# simple-hat.net
KiCad netlist of a schematic drawn in EAGLE
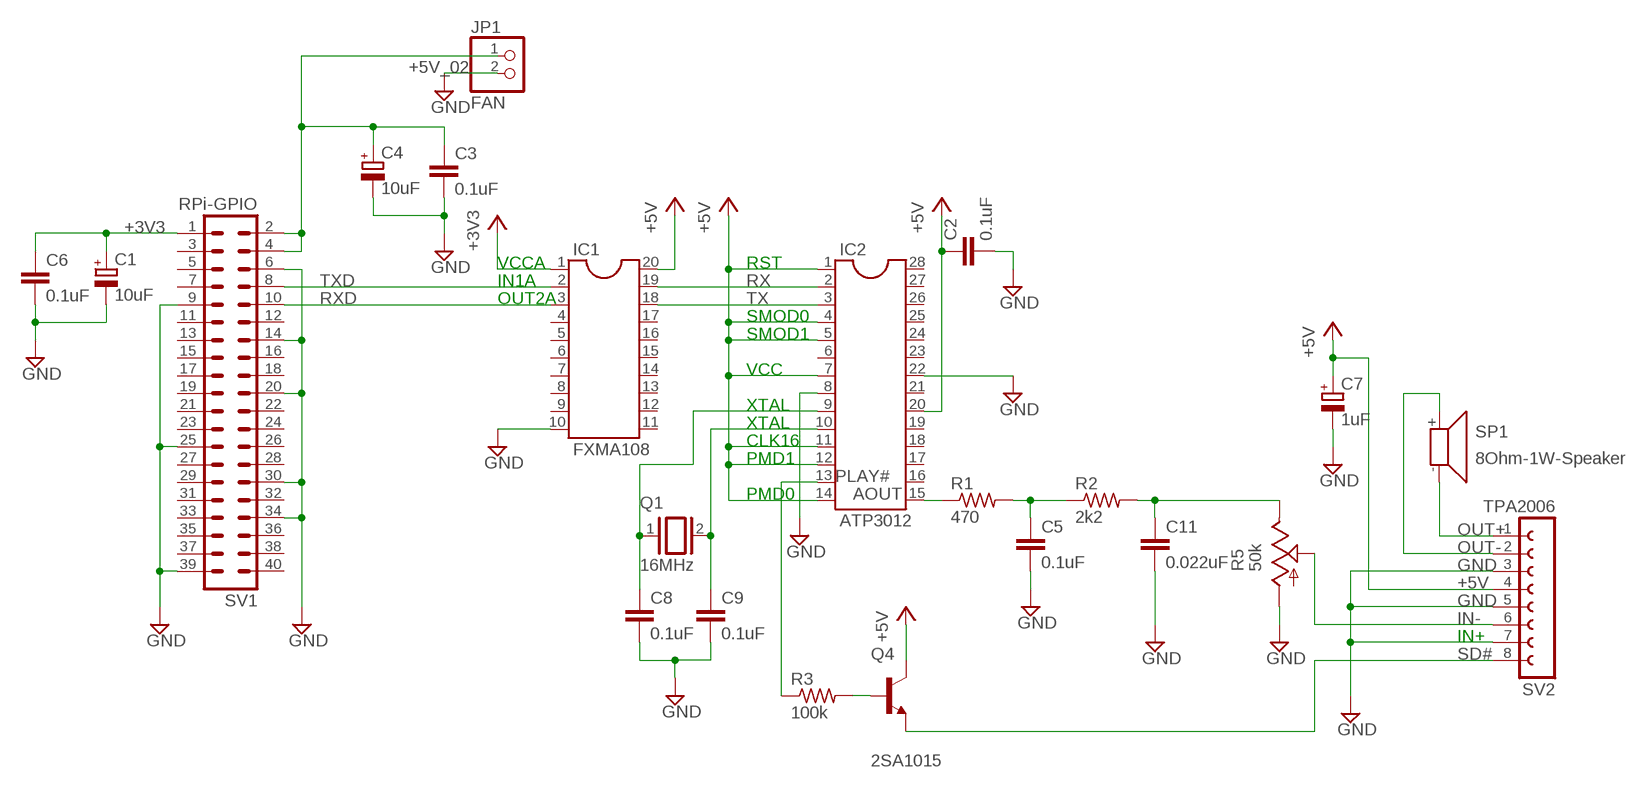
[diagram p0: schematic, sheet 1]

(export (version "E")
  (design (tool "Eeschema 10.0.6"))
  (components
    (comp (ref "C1")
      (value "10uF")
      (footprint "eagle-import:E2-5")
      (libsource (lib "eagle-import") (part "CPOL-EUE2-5"))
    )
    (comp (ref "C2")
      (value "0.1uF")
      (footprint "eagle-import:C025-025X050")
      (libsource (lib "eagle-import") (part "C-EU025-025X050"))
    )
    (comp (ref "C3")
      (value "0.1uF")
      (footprint "eagle-import:C025-025X050")
      (libsource (lib "eagle-import") (part "C-EU025-025X050"))
    )
    (comp (ref "C4")
      (value "10uF")
      (footprint "eagle-import:E2-5")
      (libsource (lib "eagle-import") (part "CPOL-EUE2-5"))
    )
    (comp (ref "C5")
      (value "0.1uF")
      (footprint "eagle-import:C025-025X050")
      (libsource (lib "eagle-import") (part "C-EU025-025X050"))
    )
    (comp (ref "C6")
      (value "0.1uF")
      (footprint "eagle-import:C025-025X050")
      (libsource (lib "eagle-import") (part "C-EU025-025X050"))
    )
    (comp (ref "C7")
      (value "1uF")
      (footprint "eagle-import:E5-10,5")
      (libsource (lib "eagle-import") (part "CPOL-EUE5-10.5"))
    )
    (comp (ref "C8")
      (value "0.1uF")
      (footprint "eagle-import:C025-025X050")
      (libsource (lib "eagle-import") (part "C-EU025-025X050"))
    )
    (comp (ref "C9")
      (value "0.1uF")
      (footprint "eagle-import:C025-025X050")
      (libsource (lib "eagle-import") (part "C-EU025-025X050"))
    )
    (comp (ref "C11")
      (value "0.022uF")
      (footprint "eagle-import:C025-025X050")
      (libsource (lib "eagle-import") (part "C-EU025-025X050"))
    )
    (comp (ref "IC1")
      (value "FXMA108")
      (footprint "eagle-import:SOCKET-20")
      (libsource (lib "eagle-import") (part "DIL20S"))
    )
    (comp (ref "IC2")
      (value "ATP3012")
      (footprint "eagle-import:DIL28-4")
      (libsource (lib "eagle-import") (part "DIL28-4"))
    )
    (comp (ref "JP1")
      (value "FAN")
      (footprint "eagle-import:1X02")
      (libsource (lib "eagle-import") (part "PINHD-1X2"))
    )
    (comp (ref "Q1")
      (value "16MHz")
      (footprint "eagle-import:Q")
      (libsource (lib "eagle-import") (part "XTAL"))
    )
    (comp (ref "Q4")
      (value "2SA1015")
      (footprint "eagle-import:TO92-EBC")
      (libsource (lib "eagle-import") (part "BC447"))
    )
    (comp (ref "R1")
      (value "470")
      (footprint "eagle-import:0207_7")
      (libsource (lib "eagle-import") (part "R-US_0207/7"))
    )
    (comp (ref "R2")
      (value "2k2")
      (footprint "eagle-import:0207_7")
      (libsource (lib "eagle-import") (part "R-US_0207/7"))
    )
    (comp (ref "R3")
      (value "100k")
      (footprint "eagle-import:0207_7")
      (libsource (lib "eagle-import") (part "R-US_0207/7"))
    )
    (comp (ref "R5")
      (value "50k")
      (footprint "eagle-import:B25P")
      (libsource (lib "eagle-import") (part "TRIM_US-B25P"))
    )
    (comp (ref "SP1")
      (value "8Ohm-1W-Speaker")
      (footprint "eagle-import:SMS-1308MS-2-R")
      (libsource (lib "eagle-import") (part "SMS-1308MS-2-R"))
    )
    (comp (ref "SV1")
      (value "RPi-GPIO")
      (footprint "eagle-import:MA20-2")
      (libsource (lib "eagle-import") (part "MA20-2"))
    )
    (comp (ref "SV2")
      (value "TPA2006")
      (footprint "eagle-import:FE08W")
      (libsource (lib "eagle-import") (part "FE08W"))
    )
  )
  (nets
    (net (code "1") (name "+3V3") (class "Default")
      (node (ref "C1") (pin "+") (pinfunction "+_+") (pintype "passive"))
      (node (ref "C6") (pin "1") (pinfunction "1_1") (pintype "passive"))
      (node (ref "IC1") (pin "1") (pinfunction "1_1") (pintype "passive"))
      (node (ref "SV1") (pin "1") (pinfunction "1_1") (pintype "passive"))
    )
    (net (code "2") (name "+5V") (class "Default")
      (node (ref "C2") (pin "1") (pinfunction "1_1") (pintype "passive"))
      (node (ref "C7") (pin "+") (pinfunction "+_+") (pintype "passive"))
      (node (ref "IC1") (pin "20") (pinfunction "20_20") (pintype "passive"))
      (node (ref "IC2") (pin "1") (pinfunction "1_1") (pintype "passive"))
      (node (ref "IC2") (pin "11") (pinfunction "11_11") (pintype "passive"))
      (node (ref "IC2") (pin "12") (pinfunction "12_12") (pintype "passive"))
      (node (ref "IC2") (pin "14") (pinfunction "14_14") (pintype "passive"))
      (node (ref "IC2") (pin "20") (pinfunction "20_20") (pintype "passive"))
      (node (ref "IC2") (pin "4") (pinfunction "4_4") (pintype "passive"))
      (node (ref "IC2") (pin "5") (pinfunction "5_5") (pintype "passive"))
      (node (ref "IC2") (pin "7") (pinfunction "7_7") (pintype "passive"))
      (node (ref "Q4") (pin "C") (pinfunction "C_C") (pintype "passive"))
      (node (ref "SV2") (pin "4") (pinfunction "4_4") (pintype "passive"))
    )
    (net (code "3") (name "/+5V_02") (class "Default")
      (node (ref "C3") (pin "1") (pinfunction "1_1") (pintype "passive"))
      (node (ref "C4") (pin "+") (pinfunction "+_+") (pintype "passive"))
      (node (ref "JP1") (pin "1") (pinfunction "1_1") (pintype "passive"))
      (node (ref "SV1") (pin "2") (pinfunction "2_2") (pintype "passive"))
      (node (ref "SV1") (pin "4") (pinfunction "4_4") (pintype "passive"))
    )
    (net (code "4") (name "/AOUT") (class "Default")
      (node (ref "IC2") (pin "15") (pinfunction "15_15") (pintype "passive"))
      (node (ref "R1") (pin "1") (pinfunction "1_1") (pintype "passive"))
    )
    (net (code "5") (name "/IN-") (class "Default")
      (node (ref "R5") (pin "S") (pinfunction "S_S") (pintype "passive"))
      (node (ref "SV2") (pin "6") (pinfunction "6_6") (pintype "passive"))
    )
    (net (code "6") (name "/OUT+") (class "Default")
      (node (ref "SP1") (pin "-") (pinfunction "2_-") (pintype "passive"))
      (node (ref "SV2") (pin "1") (pinfunction "1_1") (pintype "passive"))
    )
    (net (code "7") (name "/OUT-") (class "Default")
      (node (ref "SP1") (pin "+") (pinfunction "1_+") (pintype "passive"))
      (node (ref "SV2") (pin "2") (pinfunction "2_2") (pintype "passive"))
    )
    (net (code "8") (name "/PLAY#") (class "Default")
      (node (ref "IC2") (pin "13") (pinfunction "13_13") (pintype "passive"))
      (node (ref "R3") (pin "1") (pinfunction "1_1") (pintype "passive"))
    )
    (net (code "9") (name "/RX") (class "Default")
      (node (ref "IC1") (pin "19") (pinfunction "19_19") (pintype "passive"))
      (node (ref "IC2") (pin "2") (pinfunction "2_2") (pintype "passive"))
    )
    (net (code "10") (name "/RXD") (class "Default")
      (node (ref "IC1") (pin "3") (pinfunction "3_3") (pintype "passive"))
      (node (ref "SV1") (pin "10") (pinfunction "10_10") (pintype "passive"))
    )
    (net (code "11") (name "/SD#") (class "Default")
      (node (ref "Q4") (pin "E") (pinfunction "E_E") (pintype "passive"))
      (node (ref "SV2") (pin "8") (pinfunction "8_8") (pintype "passive"))
    )
    (net (code "12") (name "/TX") (class "Default")
      (node (ref "IC1") (pin "18") (pinfunction "18_18") (pintype "passive"))
      (node (ref "IC2") (pin "3") (pinfunction "3_3") (pintype "passive"))
    )
    (net (code "13") (name "/TXD") (class "Default")
      (node (ref "IC1") (pin "2") (pinfunction "2_2") (pintype "passive"))
      (node (ref "SV1") (pin "8") (pinfunction "8_8") (pintype "passive"))
    )
    (net (code "14") (name "GND") (class "Default")
      (node (ref "C1") (pin "-") (pinfunction "-_-") (pintype "passive"))
      (node (ref "C11") (pin "2") (pinfunction "2_2") (pintype "passive"))
      (node (ref "C2") (pin "2") (pinfunction "2_2") (pintype "passive"))
      (node (ref "C3") (pin "2") (pinfunction "2_2") (pintype "passive"))
      (node (ref "C4") (pin "-") (pinfunction "-_-") (pintype "passive"))
      (node (ref "C5") (pin "2") (pinfunction "2_2") (pintype "passive"))
      (node (ref "C6") (pin "2") (pinfunction "2_2") (pintype "passive"))
      (node (ref "C7") (pin "-") (pinfunction "-_-") (pintype "passive"))
      (node (ref "C8") (pin "2") (pinfunction "2_2") (pintype "passive"))
      (node (ref "C9") (pin "2") (pinfunction "2_2") (pintype "passive"))
      (node (ref "IC1") (pin "10") (pinfunction "10_10") (pintype "passive"))
      (node (ref "IC2") (pin "22") (pinfunction "22_22") (pintype "passive"))
      (node (ref "IC2") (pin "8") (pinfunction "8_8") (pintype "passive"))
      (node (ref "JP1") (pin "2") (pinfunction "2_2") (pintype "passive"))
      (node (ref "R5") (pin "A") (pinfunction "A_A") (pintype "passive"))
      (node (ref "SV1") (pin "14") (pinfunction "14_14") (pintype "passive"))
      (node (ref "SV1") (pin "20") (pinfunction "20_20") (pintype "passive"))
      (node (ref "SV1") (pin "25") (pinfunction "25_25") (pintype "passive"))
      (node (ref "SV1") (pin "30") (pinfunction "30_30") (pintype "passive"))
      (node (ref "SV1") (pin "34") (pinfunction "34_34") (pintype "passive"))
      (node (ref "SV1") (pin "39") (pinfunction "39_39") (pintype "passive"))
      (node (ref "SV1") (pin "6") (pinfunction "6_6") (pintype "passive"))
      (node (ref "SV1") (pin "9") (pinfunction "9_9") (pintype "passive"))
      (node (ref "SV2") (pin "3") (pinfunction "3_3") (pintype "passive"))
      (node (ref "SV2") (pin "5") (pinfunction "5_5") (pintype "passive"))
      (node (ref "SV2") (pin "7") (pinfunction "7_7") (pintype "passive"))
    )
    (net (code "15") (name "Net-(C5-Pad1)") (class "Default")
      (node (ref "C5") (pin "1") (pinfunction "1_1") (pintype "passive"))
      (node (ref "R1") (pin "2") (pinfunction "2_2") (pintype "passive"))
      (node (ref "R2") (pin "1") (pinfunction "1_1") (pintype "passive"))
    )
    (net (code "16") (name "Net-(C8-Pad1)") (class "Default")
      (node (ref "C8") (pin "1") (pinfunction "1_1") (pintype "passive"))
      (node (ref "IC2") (pin "9") (pinfunction "9_9") (pintype "passive"))
      (node (ref "Q1") (pin "1") (pinfunction "1_1") (pintype "passive"))
    )
    (net (code "17") (name "Net-(C9-Pad1)") (class "Default")
      (node (ref "C9") (pin "1") (pinfunction "1_1") (pintype "passive"))
      (node (ref "IC2") (pin "10") (pinfunction "10_10") (pintype "passive"))
      (node (ref "Q1") (pin "2") (pinfunction "2_2") (pintype "passive"))
    )
    (net (code "18") (name "Net-(C11-Pad1)") (class "Default")
      (node (ref "C11") (pin "1") (pinfunction "1_1") (pintype "passive"))
      (node (ref "R2") (pin "2") (pinfunction "2_2") (pintype "passive"))
      (node (ref "R5") (pin "E") (pinfunction "E_E") (pintype "passive"))
    )
    (net (code "19") (name "Net-(Q4-PadB)") (class "Default")
      (node (ref "Q4") (pin "B") (pinfunction "B_B") (pintype "passive"))
      (node (ref "R3") (pin "2") (pinfunction "2_2") (pintype "passive"))
    )
    (net (code "20") (name "unconnected-(IC1-Pad4)") (class "Default")
      (node (ref "IC1") (pin "4") (pinfunction "4_4") (pintype "passive"))
    )
    (net (code "21") (name "unconnected-(IC1-Pad5)") (class "Default")
      (node (ref "IC1") (pin "5") (pinfunction "5_5") (pintype "passive"))
    )
    (net (code "22") (name "unconnected-(IC1-Pad6)") (class "Default")
      (node (ref "IC1") (pin "6") (pinfunction "6_6") (pintype "passive"))
    )
    (net (code "23") (name "unconnected-(IC1-Pad7)") (class "Default")
      (node (ref "IC1") (pin "7") (pinfunction "7_7") (pintype "passive"))
    )
    (net (code "24") (name "unconnected-(IC1-Pad8)") (class "Default")
      (node (ref "IC1") (pin "8") (pinfunction "8_8") (pintype "passive"))
    )
    (net (code "25") (name "unconnected-(IC1-Pad9)") (class "Default")
      (node (ref "IC1") (pin "9") (pinfunction "9_9") (pintype "passive"))
    )
    (net (code "26") (name "unconnected-(IC1-Pad11)") (class "Default")
      (node (ref "IC1") (pin "11") (pinfunction "11_11") (pintype "passive"))
    )
    (net (code "27") (name "unconnected-(IC1-Pad12)") (class "Default")
      (node (ref "IC1") (pin "12") (pinfunction "12_12") (pintype "passive"))
    )
    (net (code "28") (name "unconnected-(IC1-Pad13)") (class "Default")
      (node (ref "IC1") (pin "13") (pinfunction "13_13") (pintype "passive"))
    )
    (net (code "29") (name "unconnected-(IC1-Pad14)") (class "Default")
      (node (ref "IC1") (pin "14") (pinfunction "14_14") (pintype "passive"))
    )
    (net (code "30") (name "unconnected-(IC1-Pad15)") (class "Default")
      (node (ref "IC1") (pin "15") (pinfunction "15_15") (pintype "passive"))
    )
    (net (code "31") (name "unconnected-(IC1-Pad16)") (class "Default")
      (node (ref "IC1") (pin "16") (pinfunction "16_16") (pintype "passive"))
    )
    (net (code "32") (name "unconnected-(IC1-Pad17)") (class "Default")
      (node (ref "IC1") (pin "17") (pinfunction "17_17") (pintype "passive"))
    )
    (net (code "33") (name "unconnected-(IC2-Pad6)") (class "Default")
      (node (ref "IC2") (pin "6") (pinfunction "6_6") (pintype "passive"))
    )
    (net (code "34") (name "unconnected-(IC2-Pad16)") (class "Default")
      (node (ref "IC2") (pin "16") (pinfunction "16_16") (pintype "passive"))
    )
    (net (code "35") (name "unconnected-(IC2-Pad17)") (class "Default")
      (node (ref "IC2") (pin "17") (pinfunction "17_17") (pintype "passive"))
    )
    (net (code "36") (name "unconnected-(IC2-Pad18)") (class "Default")
      (node (ref "IC2") (pin "18") (pinfunction "18_18") (pintype "passive"))
    )
    (net (code "37") (name "unconnected-(IC2-Pad19)") (class "Default")
      (node (ref "IC2") (pin "19") (pinfunction "19_19") (pintype "passive"))
    )
    (net (code "38") (name "unconnected-(IC2-Pad21)") (class "Default")
      (node (ref "IC2") (pin "21") (pinfunction "21_21") (pintype "passive"))
    )
    (net (code "39") (name "unconnected-(IC2-Pad23)") (class "Default")
      (node (ref "IC2") (pin "23") (pinfunction "23_23") (pintype "passive"))
    )
    (net (code "40") (name "unconnected-(IC2-Pad24)") (class "Default")
      (node (ref "IC2") (pin "24") (pinfunction "24_24") (pintype "passive"))
    )
    (net (code "41") (name "unconnected-(IC2-Pad25)") (class "Default")
      (node (ref "IC2") (pin "25") (pinfunction "25_25") (pintype "passive"))
    )
    (net (code "42") (name "unconnected-(IC2-Pad26)") (class "Default")
      (node (ref "IC2") (pin "26") (pinfunction "26_26") (pintype "passive"))
    )
    (net (code "43") (name "unconnected-(IC2-Pad27)") (class "Default")
      (node (ref "IC2") (pin "27") (pinfunction "27_27") (pintype "passive"))
    )
    (net (code "44") (name "unconnected-(IC2-Pad28)") (class "Default")
      (node (ref "IC2") (pin "28") (pinfunction "28_28") (pintype "passive"))
    )
    (net (code "45") (name "unconnected-(SV1-Pad3)") (class "Default")
      (node (ref "SV1") (pin "3") (pinfunction "3_3") (pintype "passive"))
    )
    (net (code "46") (name "unconnected-(SV1-Pad5)") (class "Default")
      (node (ref "SV1") (pin "5") (pinfunction "5_5") (pintype "passive"))
    )
    (net (code "47") (name "unconnected-(SV1-Pad7)") (class "Default")
      (node (ref "SV1") (pin "7") (pinfunction "7_7") (pintype "passive"))
    )
    (net (code "48") (name "unconnected-(SV1-Pad11)") (class "Default")
      (node (ref "SV1") (pin "11") (pinfunction "11_11") (pintype "passive"))
    )
    (net (code "49") (name "unconnected-(SV1-Pad12)") (class "Default")
      (node (ref "SV1") (pin "12") (pinfunction "12_12") (pintype "passive"))
    )
    (net (code "50") (name "unconnected-(SV1-Pad13)") (class "Default")
      (node (ref "SV1") (pin "13") (pinfunction "13_13") (pintype "passive"))
    )
    (net (code "51") (name "unconnected-(SV1-Pad15)") (class "Default")
      (node (ref "SV1") (pin "15") (pinfunction "15_15") (pintype "passive"))
    )
    (net (code "52") (name "unconnected-(SV1-Pad16)") (class "Default")
      (node (ref "SV1") (pin "16") (pinfunction "16_16") (pintype "passive"))
    )
    (net (code "53") (name "unconnected-(SV1-Pad17)") (class "Default")
      (node (ref "SV1") (pin "17") (pinfunction "17_17") (pintype "passive"))
    )
    (net (code "54") (name "unconnected-(SV1-Pad18)") (class "Default")
      (node (ref "SV1") (pin "18") (pinfunction "18_18") (pintype "passive"))
    )
    (net (code "55") (name "unconnected-(SV1-Pad19)") (class "Default")
      (node (ref "SV1") (pin "19") (pinfunction "19_19") (pintype "passive"))
    )
    (net (code "56") (name "unconnected-(SV1-Pad21)") (class "Default")
      (node (ref "SV1") (pin "21") (pinfunction "21_21") (pintype "passive"))
    )
    (net (code "57") (name "unconnected-(SV1-Pad22)") (class "Default")
      (node (ref "SV1") (pin "22") (pinfunction "22_22") (pintype "passive"))
    )
    (net (code "58") (name "unconnected-(SV1-Pad23)") (class "Default")
      (node (ref "SV1") (pin "23") (pinfunction "23_23") (pintype "passive"))
    )
    (net (code "59") (name "unconnected-(SV1-Pad24)") (class "Default")
      (node (ref "SV1") (pin "24") (pinfunction "24_24") (pintype "passive"))
    )
    (net (code "60") (name "unconnected-(SV1-Pad26)") (class "Default")
      (node (ref "SV1") (pin "26") (pinfunction "26_26") (pintype "passive"))
    )
    (net (code "61") (name "unconnected-(SV1-Pad27)") (class "Default")
      (node (ref "SV1") (pin "27") (pinfunction "27_27") (pintype "passive"))
    )
    (net (code "62") (name "unconnected-(SV1-Pad28)") (class "Default")
      (node (ref "SV1") (pin "28") (pinfunction "28_28") (pintype "passive"))
    )
    (net (code "63") (name "unconnected-(SV1-Pad29)") (class "Default")
      (node (ref "SV1") (pin "29") (pinfunction "29_29") (pintype "passive"))
    )
    (net (code "64") (name "unconnected-(SV1-Pad31)") (class "Default")
      (node (ref "SV1") (pin "31") (pinfunction "31_31") (pintype "passive"))
    )
    (net (code "65") (name "unconnected-(SV1-Pad32)") (class "Default")
      (node (ref "SV1") (pin "32") (pinfunction "32_32") (pintype "passive"))
    )
    (net (code "66") (name "unconnected-(SV1-Pad33)") (class "Default")
      (node (ref "SV1") (pin "33") (pinfunction "33_33") (pintype "passive"))
    )
    (net (code "67") (name "unconnected-(SV1-Pad35)") (class "Default")
      (node (ref "SV1") (pin "35") (pinfunction "35_35") (pintype "passive"))
    )
    (net (code "68") (name "unconnected-(SV1-Pad36)") (class "Default")
      (node (ref "SV1") (pin "36") (pinfunction "36_36") (pintype "passive"))
    )
    (net (code "69") (name "unconnected-(SV1-Pad37)") (class "Default")
      (node (ref "SV1") (pin "37") (pinfunction "37_37") (pintype "passive"))
    )
    (net (code "70") (name "unconnected-(SV1-Pad38)") (class "Default")
      (node (ref "SV1") (pin "38") (pinfunction "38_38") (pintype "passive"))
    )
    (net (code "71") (name "unconnected-(SV1-Pad40)") (class "Default")
      (node (ref "SV1") (pin "40") (pinfunction "40_40") (pintype "passive"))
    )
  )
)
